# DoorOpenerPCB.net
KiCad netlist of a schematic drawn in EAGLE
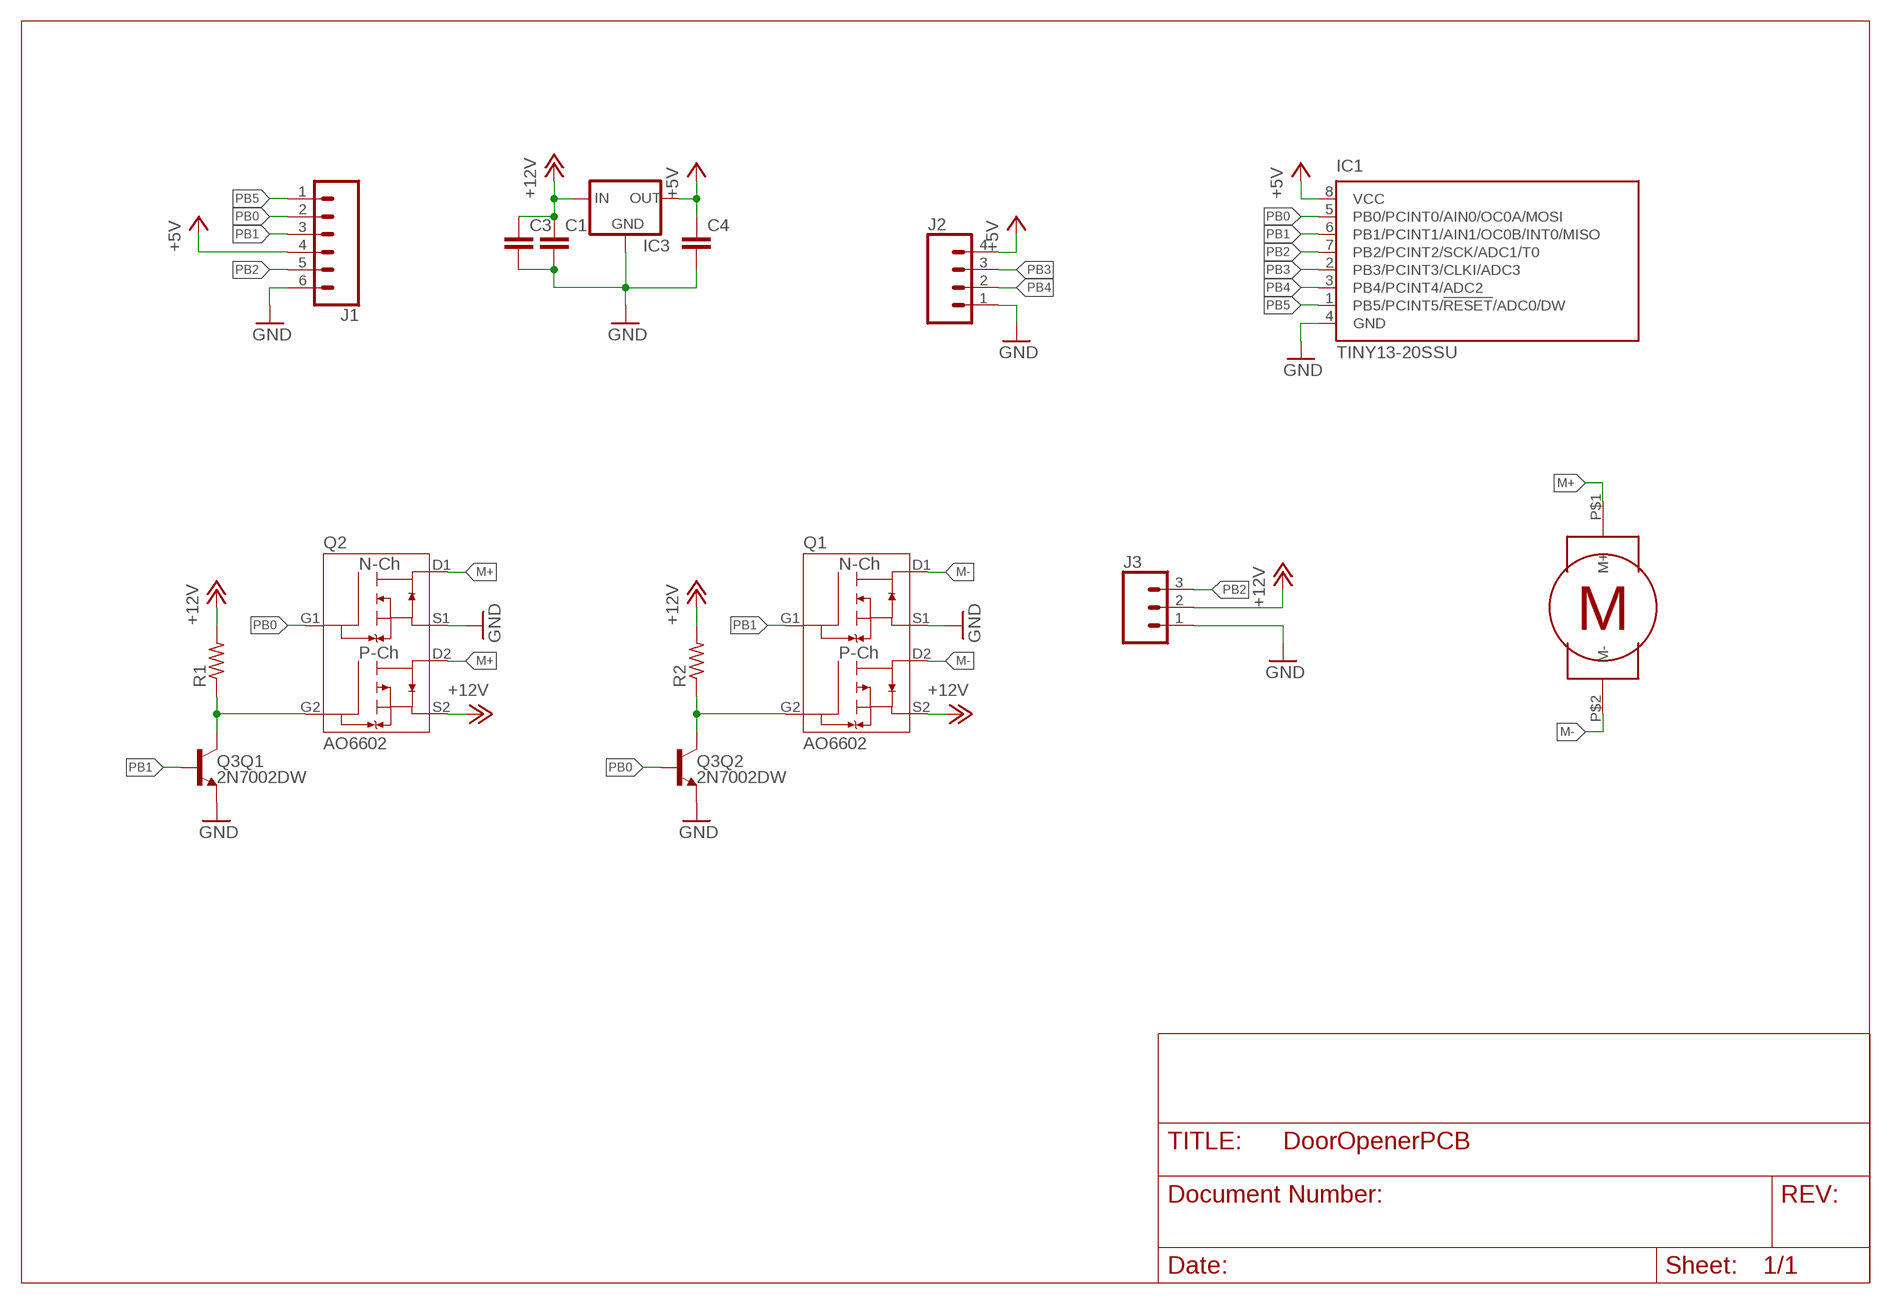
[diagram p0: schematic, sheet 1]

(export (version "E")
  (design (tool "Eeschema 10.0.6"))
  (components
    (comp (ref "C1")
      (value "C-EUC0805K")
      (footprint "eagle-import:C0805K")
      (libsource (lib "eagle-import") (part "C-EUC0805K"))
    )
    (comp (ref "C3")
      (value "C-EUC0805K")
      (footprint "eagle-import:C0805K")
      (libsource (lib "eagle-import") (part "C-EUC0805K"))
    )
    (comp (ref "C4")
      (value "C-EUC0603K")
      (footprint "eagle-import:C0603K")
      (libsource (lib "eagle-import") (part "C-EUC0603K"))
    )
    (comp (ref "IC1")
      (value "TINY13-20SSU")
      (footprint "eagle-import:8S1")
      (fields (field (name "MPN") "ATTINY13-20SSU"))
      (libsource (lib "eagle-import") (part "TINY13SSU-20"))
    )
    (comp (ref "IC3")
      (value "78LXX-SOT89R")
      (footprint "eagle-import:SOT89R")
      (libsource (lib "eagle-import") (part "78LXX-SOT89R"))
    )
    (comp (ref "J1")
      (value "CONN_061.27MM")
      (footprint "eagle-import:1X06_1.27MM")
      (libsource (lib "eagle-import") (part "CONN_061.27MM"))
    )
    (comp (ref "J2")
      (value "CONN_041.27MM")
      (footprint "eagle-import:1X04_1.27MM")
      (libsource (lib "eagle-import") (part "CONN_041.27MM"))
    )
    (comp (ref "J3")
      (value "CONN_03JST-PTH-NS")
      (footprint "eagle-import:JST-3-PTH-NS")
      (libsource (lib "eagle-import") (part "CONN_03JST-PTH-NS"))
    )
    (comp (ref "Q1")
      (value "AO6602")
      (footprint "eagle-import:SOT26")
      (libsource (lib "eagle-import") (part "MOSFET_COMPLIMENTARY_PAIR-DMC2700UDM"))
    )
    (comp (ref "Q2")
      (value "AO6602")
      (footprint "eagle-import:SOT26")
      (libsource (lib "eagle-import") (part "MOSFET_COMPLIMENTARY_PAIR-DMC2700UDM"))
    )
    (comp (ref "Q3")
      (value "2N7002DW")
      (footprint "eagle-import:SC70-6")
      (libsource (lib "eagle-import") (part "TRANS_NPN_DUAL-MBT3904DW1T1"))
    )
    (comp (ref "R1")
      (value "R-US_R0603")
      (footprint "eagle-import:R0603")
      (libsource (lib "eagle-import") (part "R-US_R0603"))
    )
    (comp (ref "R2")
      (value "R-US_R0603")
      (footprint "eagle-import:R0603")
      (libsource (lib "eagle-import") (part "R-US_R0603"))
    )
    (comp (ref "U$2")
      (value "JGY-370")
      (footprint "eagle-import:PKG")
      (libsource (lib "eagle-import") (part "JGY-370"))
    )
  )
  (nets
    (net (code "1") (name "+5V") (class "Default")
      (node (ref "C4") (pin "1") (pinfunction "1_1") (pintype "passive"))
      (node (ref "IC1") (pin "8") (pinfunction "VCC_8") (pintype "power_in"))
      (node (ref "IC3") (pin "2") (pinfunction "OUT_2") (pintype "passive"))
      (node (ref "J1") (pin "4") (pinfunction "4_4") (pintype "passive"))
      (node (ref "J2") (pin "4") (pinfunction "4_4") (pintype "passive"))
    )
    (net (code "2") (name "+12V") (class "Default")
      (node (ref "C1") (pin "1") (pinfunction "1_1") (pintype "passive"))
      (node (ref "C3") (pin "1") (pinfunction "1_1") (pintype "passive"))
      (node (ref "IC3") (pin "1") (pinfunction "IN_1") (pintype "input"))
      (node (ref "J3") (pin "2") (pinfunction "2_2") (pintype "passive"))
      (node (ref "Q1") (pin "S2") (pinfunction "S2_S2") (pintype "bidirectional"))
      (node (ref "Q2") (pin "S2") (pinfunction "S2_S2") (pintype "bidirectional"))
      (node (ref "R1") (pin "2") (pinfunction "2_2") (pintype "passive"))
      (node (ref "R2") (pin "2") (pinfunction "2_2") (pintype "passive"))
    )
    (net (code "3") (name "GND") (class "Default")
      (node (ref "C1") (pin "2") (pinfunction "2_2") (pintype "passive"))
      (node (ref "C3") (pin "2") (pinfunction "2_2") (pintype "passive"))
      (node (ref "C4") (pin "2") (pinfunction "2_2") (pintype "passive"))
      (node (ref "IC1") (pin "4") (pinfunction "GND_4") (pintype "power_in"))
      (node (ref "IC3") (pin "3") (pinfunction "GND_3") (pintype "input"))
      (node (ref "IC3") (pin "4") (pinfunction "GND_4") (pintype "input"))
      (node (ref "J1") (pin "6") (pinfunction "6_6") (pintype "passive"))
      (node (ref "J2") (pin "1") (pinfunction "1_1") (pintype "passive"))
      (node (ref "J3") (pin "1") (pinfunction "1_1") (pintype "passive"))
      (node (ref "Q1") (pin "S1") (pinfunction "S1_S1") (pintype "bidirectional"))
      (node (ref "Q2") (pin "S1") (pinfunction "S1_S1") (pintype "bidirectional"))
      (node (ref "Q3") (pin "1") (pinfunction "E_1") (pintype "passive"))
      (node (ref "Q3") (pin "4") (pinfunction "E_4") (pintype "passive"))
    )
    (net (code "4") (name "M+") (class "Default")
      (node (ref "Q2") (pin "D1") (pinfunction "D1_D1") (pintype "bidirectional"))
      (node (ref "Q2") (pin "D2") (pinfunction "D2_D2") (pintype "bidirectional"))
      (node (ref "U$2") (pin "P$1") (pinfunction "M+_P$1") (pintype "bidirectional"))
    )
    (net (code "5") (name "M-") (class "Default")
      (node (ref "Q1") (pin "D1") (pinfunction "D1_D1") (pintype "bidirectional"))
      (node (ref "Q1") (pin "D2") (pinfunction "D2_D2") (pintype "bidirectional"))
      (node (ref "U$2") (pin "P$2") (pinfunction "M-_P$2") (pintype "bidirectional"))
    )
    (net (code "6") (name "Net-(Q3A-C)") (class "Default")
      (node (ref "Q2") (pin "G2") (pinfunction "G2_G2") (pintype "bidirectional"))
      (node (ref "Q3") (pin "3") (pinfunction "C_3") (pintype "passive"))
      (node (ref "R1") (pin "1") (pinfunction "1_1") (pintype "passive"))
    )
    (net (code "7") (name "Net-(Q3B-C)") (class "Default")
      (node (ref "Q1") (pin "G2") (pinfunction "G2_G2") (pintype "bidirectional"))
      (node (ref "Q3") (pin "6") (pinfunction "C_6") (pintype "passive"))
      (node (ref "R2") (pin "1") (pinfunction "1_1") (pintype "passive"))
    )
    (net (code "8") (name "PB0") (class "Default")
      (node (ref "IC1") (pin "5") (pinfunction "PB0/PCINT0/AIN0/OC0A/MOSI_5") (pintype "bidirectional"))
      (node (ref "J1") (pin "2") (pinfunction "2_2") (pintype "passive"))
      (node (ref "Q2") (pin "G1") (pinfunction "G1_G1") (pintype "bidirectional"))
      (node (ref "Q3") (pin "2") (pinfunction "B_2") (pintype "passive"))
    )
    (net (code "9") (name "PB1") (class "Default")
      (node (ref "IC1") (pin "6") (pinfunction "PB1/PCINT1/AIN1/OC0B/INT0/MISO_6") (pintype "bidirectional"))
      (node (ref "J1") (pin "3") (pinfunction "3_3") (pintype "passive"))
      (node (ref "Q1") (pin "G1") (pinfunction "G1_G1") (pintype "bidirectional"))
      (node (ref "Q3") (pin "5") (pinfunction "B_5") (pintype "passive"))
    )
    (net (code "10") (name "PB2") (class "Default")
      (node (ref "IC1") (pin "7") (pinfunction "PB2/PCINT2/SCK/ADC1/T0_7") (pintype "bidirectional"))
      (node (ref "J1") (pin "5") (pinfunction "5_5") (pintype "passive"))
      (node (ref "J3") (pin "3") (pinfunction "3_3") (pintype "passive"))
    )
    (net (code "11") (name "PB3") (class "Default")
      (node (ref "IC1") (pin "2") (pinfunction "PB3/PCINT3/CLKI/ADC3_2") (pintype "bidirectional"))
      (node (ref "J2") (pin "3") (pinfunction "3_3") (pintype "passive"))
    )
    (net (code "12") (name "PB4") (class "Default")
      (node (ref "IC1") (pin "3") (pinfunction "PB4/PCINT4/ADC2_3") (pintype "bidirectional"))
      (node (ref "J2") (pin "2") (pinfunction "2_2") (pintype "passive"))
    )
    (net (code "13") (name "PB5") (class "Default")
      (node (ref "IC1") (pin "1") (pinfunction "PB5/PCINT5/~{RESET}/ADC0/DW_1") (pintype "bidirectional"))
      (node (ref "J1") (pin "1") (pinfunction "1_1") (pintype "passive"))
    )
  )
)
